# RaphaelJDDS_I_BLDC_1__Schematics__Sheet_.net
KiCad netlist of a schematic drawn in Altium Designer
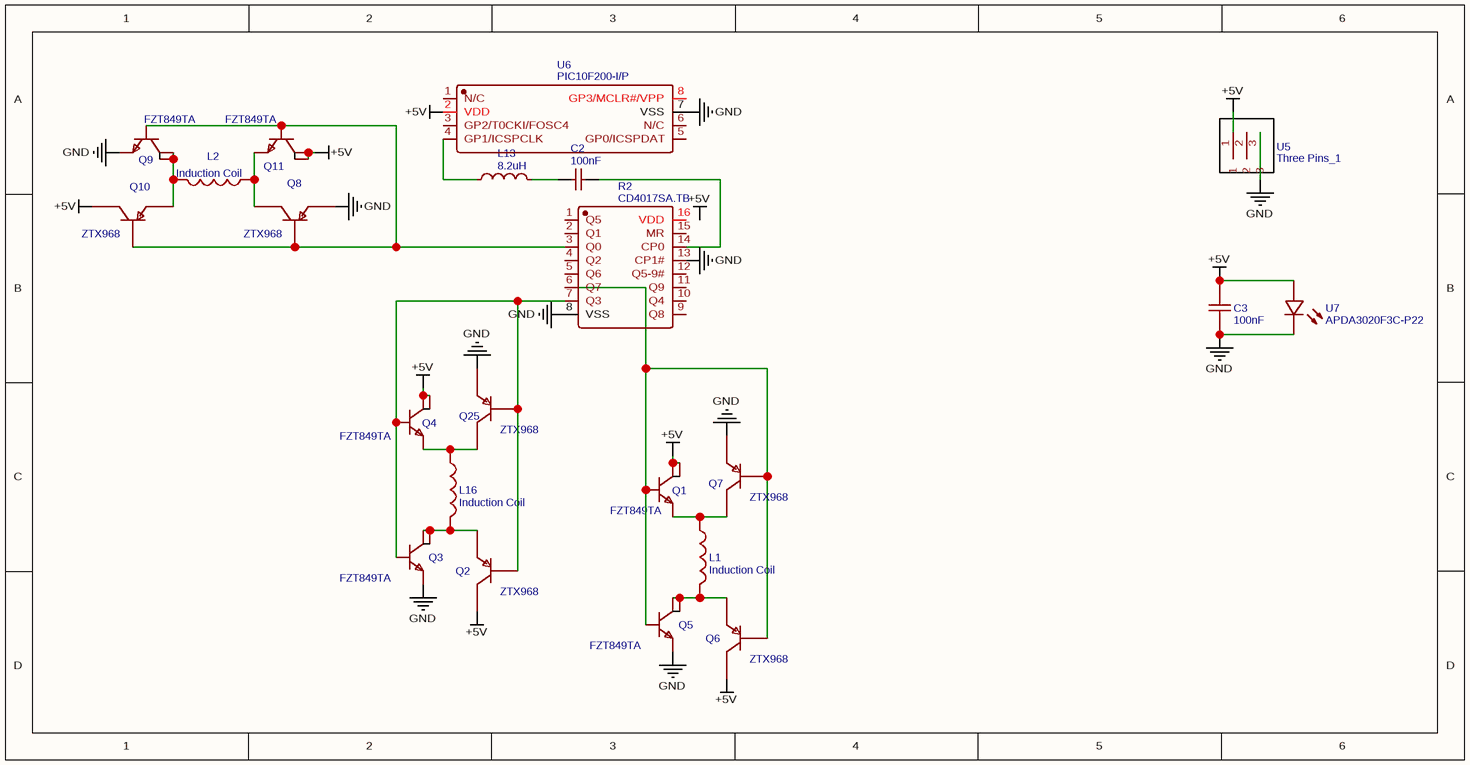
[diagram p0: RaphaelJDDS_I_BLDC_1__Schematics__Sheet_1_2025-01-21.schdoc]

(export (version "E")
  (design (tool "Eeschema 10.0.6"))
  (components
    (comp (ref "C2")
      (value "100nF")
      (fields
        (field (name "MANUFACTURER") "ReliaPro")
        (field (name "MANUFACTURER PART") "Calibration capacitor100nF（104）100V,5%")
      )
      (libsource (lib "altium-import") (part "root_0_100nF_"))
    )
    (comp (ref "C3")
      (value "100nF")
      (fields
        (field (name "MANUFACTURER") "muRata(村田)")
        (field (name "MANUFACTURER PART") "GRM188R72A104KA35D")
      )
      (libsource (lib "altium-import") (part "root_1_100nF_"))
    )
    (comp (ref "L1")
      (value "Induction Coil")
      (fields (field (name "CONTRIBUTOR") "junlakan67"))
      (libsource (lib "altium-import") (part "root_3_Induction Coil_"))
    )
    (comp (ref "L2")
      (value "Induction Coil")
      (fields (field (name "CONTRIBUTOR") "junlakan67"))
      (libsource (lib "altium-import") (part "root_2_Induction Coil_"))
    )
    (comp (ref "L13")
      (value "8.2uH")
      (fields (field (name "MANUFACTURER") "SXN(顺翔诺)") (field (name "MANUFACTURER PART") "SMRH5D28-8R2NT"))
      (libsource (lib "altium-import") (part "root_0_8.2uH_"))
    )
    (comp (ref "L16")
      (value "Induction Coil")
      (fields (field (name "CONTRIBUTOR") "junlakan67"))
      (libsource (lib "altium-import") (part "root_3_Induction Coil_"))
    )
    (comp (ref "Q1")
      (value "ZTX968")
      (description "PNP Silicon Planar Medium Power High-Current Transistor")
      (libsource (lib "altium-import") (part "root_0_ZTX968_"))
    )
    (comp (ref "Q2")
      (value "ZTX968")
      (description "PNP Silicon Planar Medium Power High-Current Transistor")
      (libsource (lib "altium-import") (part "root_0_ZTX968_"))
    )
    (comp (ref "Q3")
      (value "FZT849TA")
      (fields (field (name "MANUFACTURER") "DIODES(美台)"))
      (libsource (lib "altium-import") (part "root_2_FZT849TA_"))
    )
    (comp (ref "Q4")
      (value "ZTX968")
      (description "PNP Silicon Planar Medium Power High-Current Transistor")
      (libsource (lib "altium-import") (part "root_0_ZTX968_"))
    )
    (comp (ref "Q5")
      (value "FZT849TA")
      (fields (field (name "MANUFACTURER") "DIODES(美台)"))
      (libsource (lib "altium-import") (part "root_2_FZT849TA_"))
    )
    (comp (ref "Q6")
      (value "ZTX968")
      (description "PNP Silicon Planar Medium Power High-Current Transistor")
      (libsource (lib "altium-import") (part "root_0_ZTX968_"))
    )
    (comp (ref "Q7")
      (value "FZT849TA")
      (fields (field (name "MANUFACTURER") "DIODES(美台)"))
      (libsource (lib "altium-import") (part "root_2_FZT849TA_"))
    )
    (comp (ref "Q8")
      (value "ZTX968")
      (description "PNP Silicon Planar Medium Power High-Current Transistor")
      (libsource (lib "altium-import") (part "root_3_ZTX968_"))
    )
    (comp (ref "Q9")
      (value "FZT849TA")
      (fields (field (name "MANUFACTURER") "DIODES(美台)"))
      (libsource (lib "altium-import") (part "root_1_FZT849TA_"))
    )
    (comp (ref "Q10")
      (value "ZTX968")
      (description "PNP Silicon Planar Medium Power High-Current Transistor")
      (libsource (lib "altium-import") (part "root_3_ZTX968_"))
    )
    (comp (ref "Q11")
      (value "FZT849TA")
      (fields (field (name "MANUFACTURER") "DIODES(美台)"))
      (libsource (lib "altium-import") (part "root_1_FZT849TA_"))
    )
    (comp (ref "Q25")
      (value "FZT849TA")
      (fields (field (name "MANUFACTURER") "DIODES(美台)"))
      (libsource (lib "altium-import") (part "root_2_FZT849TA_"))
    )
    (comp (ref "R2")
      (value "CD4017SA.TB")
      (fields (field (name "MANUFACTURER") "I-CORE(中微爱芯)") (field (name "CONTRIBUTOR") "LCSC"))
      (libsource (lib "altium-import") (part "root_0_CD4017SA.TB_"))
    )
    (comp (ref "U5")
      (value "Three Pins_1")
      (fields (field (name "CONTRIBUTOR") "admon.alsamano"))
      (libsource (lib "altium-import") (part "root_0_Three Pins_1_"))
    )
    (comp (ref "U6")
      (value "PIC10F200-I/P")
      (fields (field (name "MANUFACTURER") "MICROCHIP(美国微芯)") (field (name "CONTRIBUTOR") "lcsc"))
      (libsource (lib "altium-import") (part "root_0_PIC10F200-I/P_"))
    )
    (comp (ref "U7")
      (value "APDA3020F3C-P22")
      (fields (field (name "MANUFACTURER") "Kingbright") (field (name "CONTRIBUTOR") "lcsc"))
      (libsource (lib "altium-import") (part "root_3_APDA3020F3C-P22_"))
    )
  )
  (nets
    (net (code "1") (name "+5V") (class "Default")
      (node (ref "C3") (pin "2") (pinfunction "2_2") (pintype "passive"))
      (node (ref "Q10") (pin "1") (pinfunction "C_1") (pintype "passive"))
      (node (ref "Q11") (pin "2") (pinfunction "C_2") (pintype "passive"))
      (node (ref "Q11") (pin "4") (pinfunction "C_4") (pintype "passive"))
      (node (ref "Q2") (pin "1") (pinfunction "C_1") (pintype "passive"))
      (node (ref "Q25") (pin "2") (pinfunction "C_2") (pintype "passive"))
      (node (ref "Q25") (pin "4") (pinfunction "C_4") (pintype "passive"))
      (node (ref "Q6") (pin "1") (pinfunction "C_1") (pintype "passive"))
      (node (ref "Q7") (pin "2") (pinfunction "C_2") (pintype "passive"))
      (node (ref "Q7") (pin "4") (pinfunction "C_4") (pintype "passive"))
      (node (ref "U5") (pin "1") (pinfunction "1_1") (pintype "passive"))
      (node (ref "U6") (pin "2") (pinfunction "VDD_2") (pintype "passive"))
      (node (ref "U7") (pin "2") (pinfunction "A_2") (pintype "passive"))
    )
    (net (code "2") (name "GND") (class "Default")
      (node (ref "C3") (pin "1") (pinfunction "1_1") (pintype "passive"))
      (node (ref "Q1") (pin "3") (pinfunction "E_3") (pintype "passive"))
      (node (ref "Q3") (pin "3") (pinfunction "E_3") (pintype "passive"))
      (node (ref "Q4") (pin "3") (pinfunction "E_3") (pintype "passive"))
      (node (ref "Q5") (pin "3") (pinfunction "E_3") (pintype "passive"))
      (node (ref "Q8") (pin "3") (pinfunction "E_3") (pintype "passive"))
      (node (ref "Q9") (pin "3") (pinfunction "E_3") (pintype "passive"))
      (node (ref "R2") (pin "13") (pinfunction "CP1#_13") (pintype "passive"))
      (node (ref "R2") (pin "8") (pinfunction "VSS_8") (pintype "passive"))
      (node (ref "U5") (pin "3") (pinfunction "3_3") (pintype "passive"))
      (node (ref "U6") (pin "7") (pinfunction "VSS_7") (pintype "passive"))
      (node (ref "U7") (pin "1") (pinfunction "C_1") (pintype "passive"))
    )
    (net (code "3") (name "Net-(C2-Pad1)") (class "Default")
      (node (ref "C2") (pin "1") (pinfunction "1_1") (pintype "passive"))
      (node (ref "L13") (pin "2") (pinfunction "2_2") (pintype "passive"))
    )
    (net (code "4") (name "Net-(Q1-B)") (class "Default")
      (node (ref "Q1") (pin "2") (pinfunction "B_2") (pintype "passive"))
      (node (ref "Q5") (pin "1") (pinfunction "B_1") (pintype "passive"))
      (node (ref "Q6") (pin "2") (pinfunction "B_2") (pintype "passive"))
      (node (ref "Q7") (pin "1") (pinfunction "B_1") (pintype "passive"))
      (node (ref "R2") (pin "6") (pinfunction "Q7_6") (pintype "passive"))
    )
    (net (code "5") (name "Net-(Q1-C)") (class "Default")
      (node (ref "L1") (pin "1") (pinfunction "1_1") (pintype "passive"))
      (node (ref "Q1") (pin "1") (pinfunction "C_1") (pintype "passive"))
      (node (ref "Q7") (pin "3") (pinfunction "E_3") (pintype "passive"))
    )
    (net (code "6") (name "Net-(Q2-B)") (class "Default")
      (node (ref "Q2") (pin "2") (pinfunction "B_2") (pintype "passive"))
      (node (ref "Q25") (pin "1") (pinfunction "B_1") (pintype "passive"))
      (node (ref "Q3") (pin "1") (pinfunction "B_1") (pintype "passive"))
      (node (ref "Q4") (pin "2") (pinfunction "B_2") (pintype "passive"))
      (node (ref "R2") (pin "7") (pinfunction "Q3_7") (pintype "passive"))
    )
    (net (code "7") (name "Net-(Q2-E)") (class "Default")
      (node (ref "L16") (pin "2") (pinfunction "2_2") (pintype "passive"))
      (node (ref "Q2") (pin "3") (pinfunction "E_3") (pintype "passive"))
      (node (ref "Q3") (pin "2") (pinfunction "C_2") (pintype "passive"))
      (node (ref "Q3") (pin "4") (pinfunction "C_4") (pintype "passive"))
    )
    (net (code "8") (name "Net-(Q6-E)") (class "Default")
      (node (ref "L1") (pin "2") (pinfunction "2_2") (pintype "passive"))
      (node (ref "Q5") (pin "2") (pinfunction "C_2") (pintype "passive"))
      (node (ref "Q5") (pin "4") (pinfunction "C_4") (pintype "passive"))
      (node (ref "Q6") (pin "3") (pinfunction "E_3") (pintype "passive"))
    )
    (net (code "9") (name "Net-(Q10-B)") (class "Default")
      (node (ref "Q10") (pin "2") (pinfunction "B_2") (pintype "passive"))
      (node (ref "Q11") (pin "1") (pinfunction "B_1") (pintype "passive"))
      (node (ref "Q8") (pin "2") (pinfunction "B_2") (pintype "passive"))
      (node (ref "Q9") (pin "1") (pinfunction "B_1") (pintype "passive"))
      (node (ref "R2") (pin "3") (pinfunction "Q0_3") (pintype "passive"))
    )
    (net (code "10") (name "Net-(Q10-E)") (class "Default")
      (node (ref "L2") (pin "2") (pinfunction "2_2") (pintype "passive"))
      (node (ref "Q10") (pin "3") (pinfunction "E_3") (pintype "passive"))
      (node (ref "Q9") (pin "2") (pinfunction "C_2") (pintype "passive"))
      (node (ref "Q9") (pin "4") (pinfunction "C_4") (pintype "passive"))
    )
    (net (code "11") (name "Net-(Q11-E)") (class "Default")
      (node (ref "L2") (pin "1") (pinfunction "1_1") (pintype "passive"))
      (node (ref "Q11") (pin "3") (pinfunction "E_3") (pintype "passive"))
      (node (ref "Q8") (pin "1") (pinfunction "C_1") (pintype "passive"))
    )
    (net (code "12") (name "Net-(Q25-E)") (class "Default")
      (node (ref "L16") (pin "1") (pinfunction "1_1") (pintype "passive"))
      (node (ref "Q25") (pin "3") (pinfunction "E_3") (pintype "passive"))
      (node (ref "Q4") (pin "1") (pinfunction "C_1") (pintype "passive"))
    )
    (net (code "13") (name "Net-(R2-CP0)") (class "Default")
      (node (ref "C2") (pin "2") (pinfunction "2_2") (pintype "passive"))
      (node (ref "R2") (pin "14") (pinfunction "CP0_14") (pintype "passive"))
    )
    (net (code "14") (name "Net-(U6-GP1{slash}ICSPCLK)") (class "Default")
      (node (ref "L13") (pin "1") (pinfunction "1_1") (pintype "passive"))
      (node (ref "U6") (pin "4") (pinfunction "GP1/ICSPCLK_4") (pintype "passive"))
    )
    (net (code "15") (name "unconnected-(R2-MR-Pad15)") (class "Default")
      (node (ref "R2") (pin "15") (pinfunction "MR_15") (pintype "passive"))
    )
    (net (code "16") (name "unconnected-(R2-Q1-Pad2)") (class "Default")
      (node (ref "R2") (pin "2") (pinfunction "Q1_2") (pintype "passive"))
    )
    (net (code "17") (name "unconnected-(R2-Q2-Pad4)") (class "Default")
      (node (ref "R2") (pin "4") (pinfunction "Q2_4") (pintype "passive"))
    )
    (net (code "18") (name "unconnected-(R2-Q4-Pad10)") (class "Default")
      (node (ref "R2") (pin "10") (pinfunction "Q4_10") (pintype "passive"))
    )
    (net (code "19") (name "unconnected-(R2-Q5-9#-Pad12)") (class "Default")
      (node (ref "R2") (pin "12") (pinfunction "Q5-9#_12") (pintype "passive"))
    )
    (net (code "20") (name "unconnected-(R2-Q5-Pad1)") (class "Default")
      (node (ref "R2") (pin "1") (pinfunction "Q5_1") (pintype "passive"))
    )
    (net (code "21") (name "unconnected-(R2-Q6-Pad5)") (class "Default")
      (node (ref "R2") (pin "5") (pinfunction "Q6_5") (pintype "passive"))
    )
    (net (code "22") (name "unconnected-(R2-Q8-Pad9)") (class "Default")
      (node (ref "R2") (pin "9") (pinfunction "Q8_9") (pintype "passive"))
    )
    (net (code "23") (name "unconnected-(R2-Q9-Pad11)") (class "Default")
      (node (ref "R2") (pin "11") (pinfunction "Q9_11") (pintype "passive"))
    )
    (net (code "24") (name "unconnected-(R2-VDD-Pad16)") (class "Default")
      (node (ref "R2") (pin "16") (pinfunction "VDD_16") (pintype "passive"))
    )
    (net (code "25") (name "unconnected-(U5-Pad2)") (class "Default")
      (node (ref "U5") (pin "2") (pinfunction "2_2") (pintype "passive"))
    )
    (net (code "26") (name "unconnected-(U6-GP0{slash}ICSPDAT-Pad5)") (class "Default")
      (node (ref "U6") (pin "5") (pinfunction "GP0/ICSPDAT_5") (pintype "passive"))
    )
    (net (code "27") (name "unconnected-(U6-GP2{slash}T0CKI{slash}FOSC4-Pad3)") (class "Default")
      (node (ref "U6") (pin "3") (pinfunction "GP2/T0CKI/FOSC4_3") (pintype "passive"))
    )
    (net (code "28") (name "unconnected-(U6-GP3{slash}MCLR#{slash}VPP-Pad8)") (class "Default")
      (node (ref "U6") (pin "8") (pinfunction "GP3/MCLR#/VPP_8") (pintype "passive"))
    )
    (net (code "29") (name "unconnected-(U6-N{slash}C-Pad1)") (class "Default")
      (node (ref "U6") (pin "1") (pinfunction "N/C_1") (pintype "passive"))
    )
    (net (code "30") (name "unconnected-(U6-N{slash}C-Pad6)") (class "Default")
      (node (ref "U6") (pin "6") (pinfunction "N/C_6") (pintype "passive"))
    )
  )
)
